# fans.net
KiCad netlist of a schematic drawn in Altium Designer
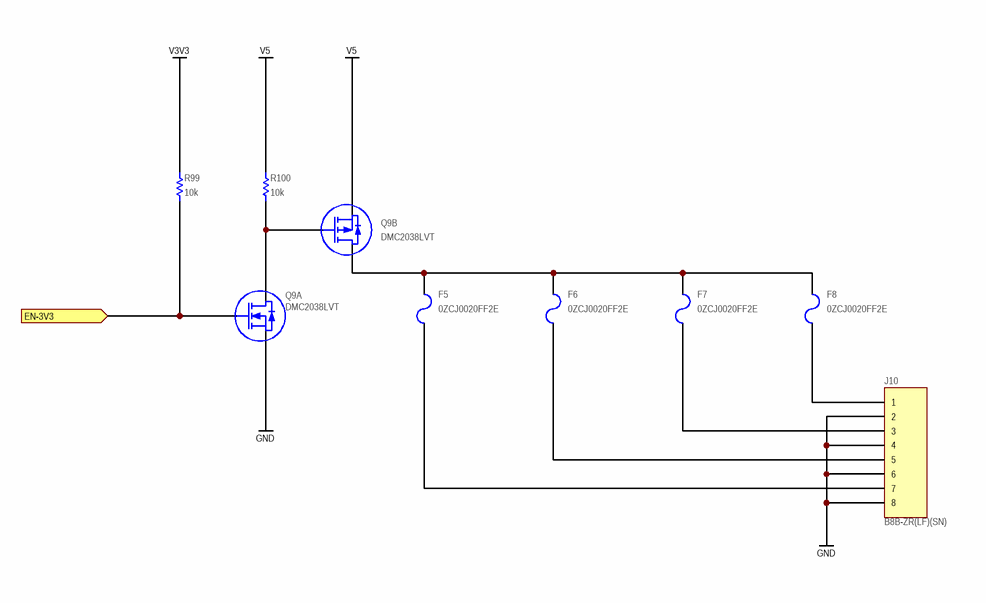
[diagram p0: fans.SchDoc]

(export (version "E")
  (design (tool "Eeschema 10.0.6"))
  (components
    (comp (ref "F5")
      (value "0ZCJ0020FF2E")
      (footprint "generic:1206")
      (description "PTC Resettable Fuse, 0.2A, 30V, SMD 1206")
      (fields (field (name "MANUFACTURER") "Bell Fuse"))
      (libsource (lib "bel-fuse") (part "0ZCJ0020FF2E"))
    )
    (comp (ref "F6")
      (value "0ZCJ0020FF2E")
      (footprint "generic:1206")
      (description "PTC Resettable Fuse, 0.2A, 30V, SMD 1206")
      (fields (field (name "MANUFACTURER") "Bell Fuse"))
      (libsource (lib "bel-fuse") (part "0ZCJ0020FF2E"))
    )
    (comp (ref "F7")
      (value "0ZCJ0020FF2E")
      (footprint "generic:1206")
      (description "PTC Resettable Fuse, 0.2A, 30V, SMD 1206")
      (fields (field (name "MANUFACTURER") "Bell Fuse"))
      (libsource (lib "bel-fuse") (part "0ZCJ0020FF2E"))
    )
    (comp (ref "F8")
      (value "0ZCJ0020FF2E")
      (footprint "generic:1206")
      (description "PTC Resettable Fuse, 0.2A, 30V, SMD 1206")
      (fields (field (name "MANUFACTURER") "Bell Fuse"))
      (libsource (lib "bel-fuse") (part "0ZCJ0020FF2E"))
    )
    (comp (ref "J10")
      (value "B8B-ZR(LF)(SN)")
      (footprint "jst:B8B-ZR")
      (description "Through-hole Shrouded Header 8-Position")
      (fields (field (name "MANUFACTURER") "JST"))
      (libsource (lib "Miscellaneous Connectors") (part "Header 8"))
    )
    (comp (ref "Q9")
      (value "DMC2038LVT")
      (footprint "generic:TSOP-6")
      (description "Complementary MOSFET Pair")
      (fields (field (name "MANUFACTURER") "Diodes, Inc."))
      (libsource (lib "diodes_inc") (part "DMC2038LVT"))
    )
    (comp (ref "R99")
      (value "10k")
      (footprint "RESC1005X40N")
      (description "Thick Film Resistor 10k ±1% 0.1W 50V 0402")
      (fields (field (name "MANUFACTURER") "Panasonic") (field (name "TOLERANCE") "±1%"))
      (libsource (lib "generic") (part "RES"))
    )
    (comp (ref "R100")
      (value "10k")
      (footprint "RESC1005X40N")
      (description "Thick Film Resistor 10k ±1% 0.1W 50V 0402")
      (fields (field (name "MANUFACTURER") "Panasonic") (field (name "TOLERANCE") "±1%"))
      (libsource (lib "generic") (part "RES"))
    )
  )
  (nets
    (net (code "1") (name "/EN-3V3") (class "Default")
      (node (ref "Q9") (pin "1") (pinfunction "G_1") (pintype "passive"))
      (node (ref "R99") (pin "1") (pinfunction "1_1") (pintype "passive"))
    )
    (net (code "2") (name "GND") (class "Default")
      (node (ref "J10") (pin "2") (pinfunction "2_2") (pintype "passive"))
      (node (ref "J10") (pin "4") (pinfunction "4_4") (pintype "passive"))
      (node (ref "J10") (pin "6") (pinfunction "6_6") (pintype "passive"))
      (node (ref "J10") (pin "8") (pinfunction "8_8") (pintype "passive"))
      (node (ref "Q9") (pin "5") (pinfunction "S_5") (pintype "passive"))
    )
    (net (code "3") (name "Net-(F5-Pad2)") (class "Default")
      (node (ref "F5") (pin "2") (pinfunction "2_2") (pintype "passive"))
      (node (ref "J10") (pin "7") (pinfunction "7_7") (pintype "passive"))
    )
    (net (code "4") (name "Net-(F6-Pad2)") (class "Default")
      (node (ref "F6") (pin "2") (pinfunction "2_2") (pintype "passive"))
      (node (ref "J10") (pin "5") (pinfunction "5_5") (pintype "passive"))
    )
    (net (code "5") (name "Net-(F7-Pad2)") (class "Default")
      (node (ref "F7") (pin "2") (pinfunction "2_2") (pintype "passive"))
      (node (ref "J10") (pin "3") (pinfunction "3_3") (pintype "passive"))
    )
    (net (code "6") (name "Net-(F8-Pad2)") (class "Default")
      (node (ref "F8") (pin "2") (pinfunction "2_2") (pintype "passive"))
      (node (ref "J10") (pin "1") (pinfunction "1_1") (pintype "passive"))
    )
    (net (code "7") (name "Net-(Q9A-D)") (class "Default")
      (node (ref "Q9") (pin "3") (pinfunction "G_3") (pintype "passive"))
      (node (ref "Q9") (pin "6") (pinfunction "D_6") (pintype "passive"))
      (node (ref "R100") (pin "1") (pinfunction "1_1") (pintype "passive"))
    )
    (net (code "8") (name "Net-(Q9B-D)") (class "Default")
      (node (ref "F5") (pin "1") (pinfunction "1_1") (pintype "passive"))
      (node (ref "F6") (pin "1") (pinfunction "1_1") (pintype "passive"))
      (node (ref "F7") (pin "1") (pinfunction "1_1") (pintype "passive"))
      (node (ref "F8") (pin "1") (pinfunction "1_1") (pintype "passive"))
      (node (ref "Q9") (pin "4") (pinfunction "D_4") (pintype "passive"))
    )
    (net (code "9") (name "V3V3") (class "Default")
      (node (ref "R99") (pin "2") (pinfunction "2_2") (pintype "passive"))
    )
    (net (code "10") (name "V5") (class "Default")
      (node (ref "Q9") (pin "2") (pinfunction "S_2") (pintype "passive"))
      (node (ref "R100") (pin "2") (pinfunction "2_2") (pintype "passive"))
    )
  )
)
